# d725-pwm-dco.net
KiCad netlist of a schematic drawn in EAGLE
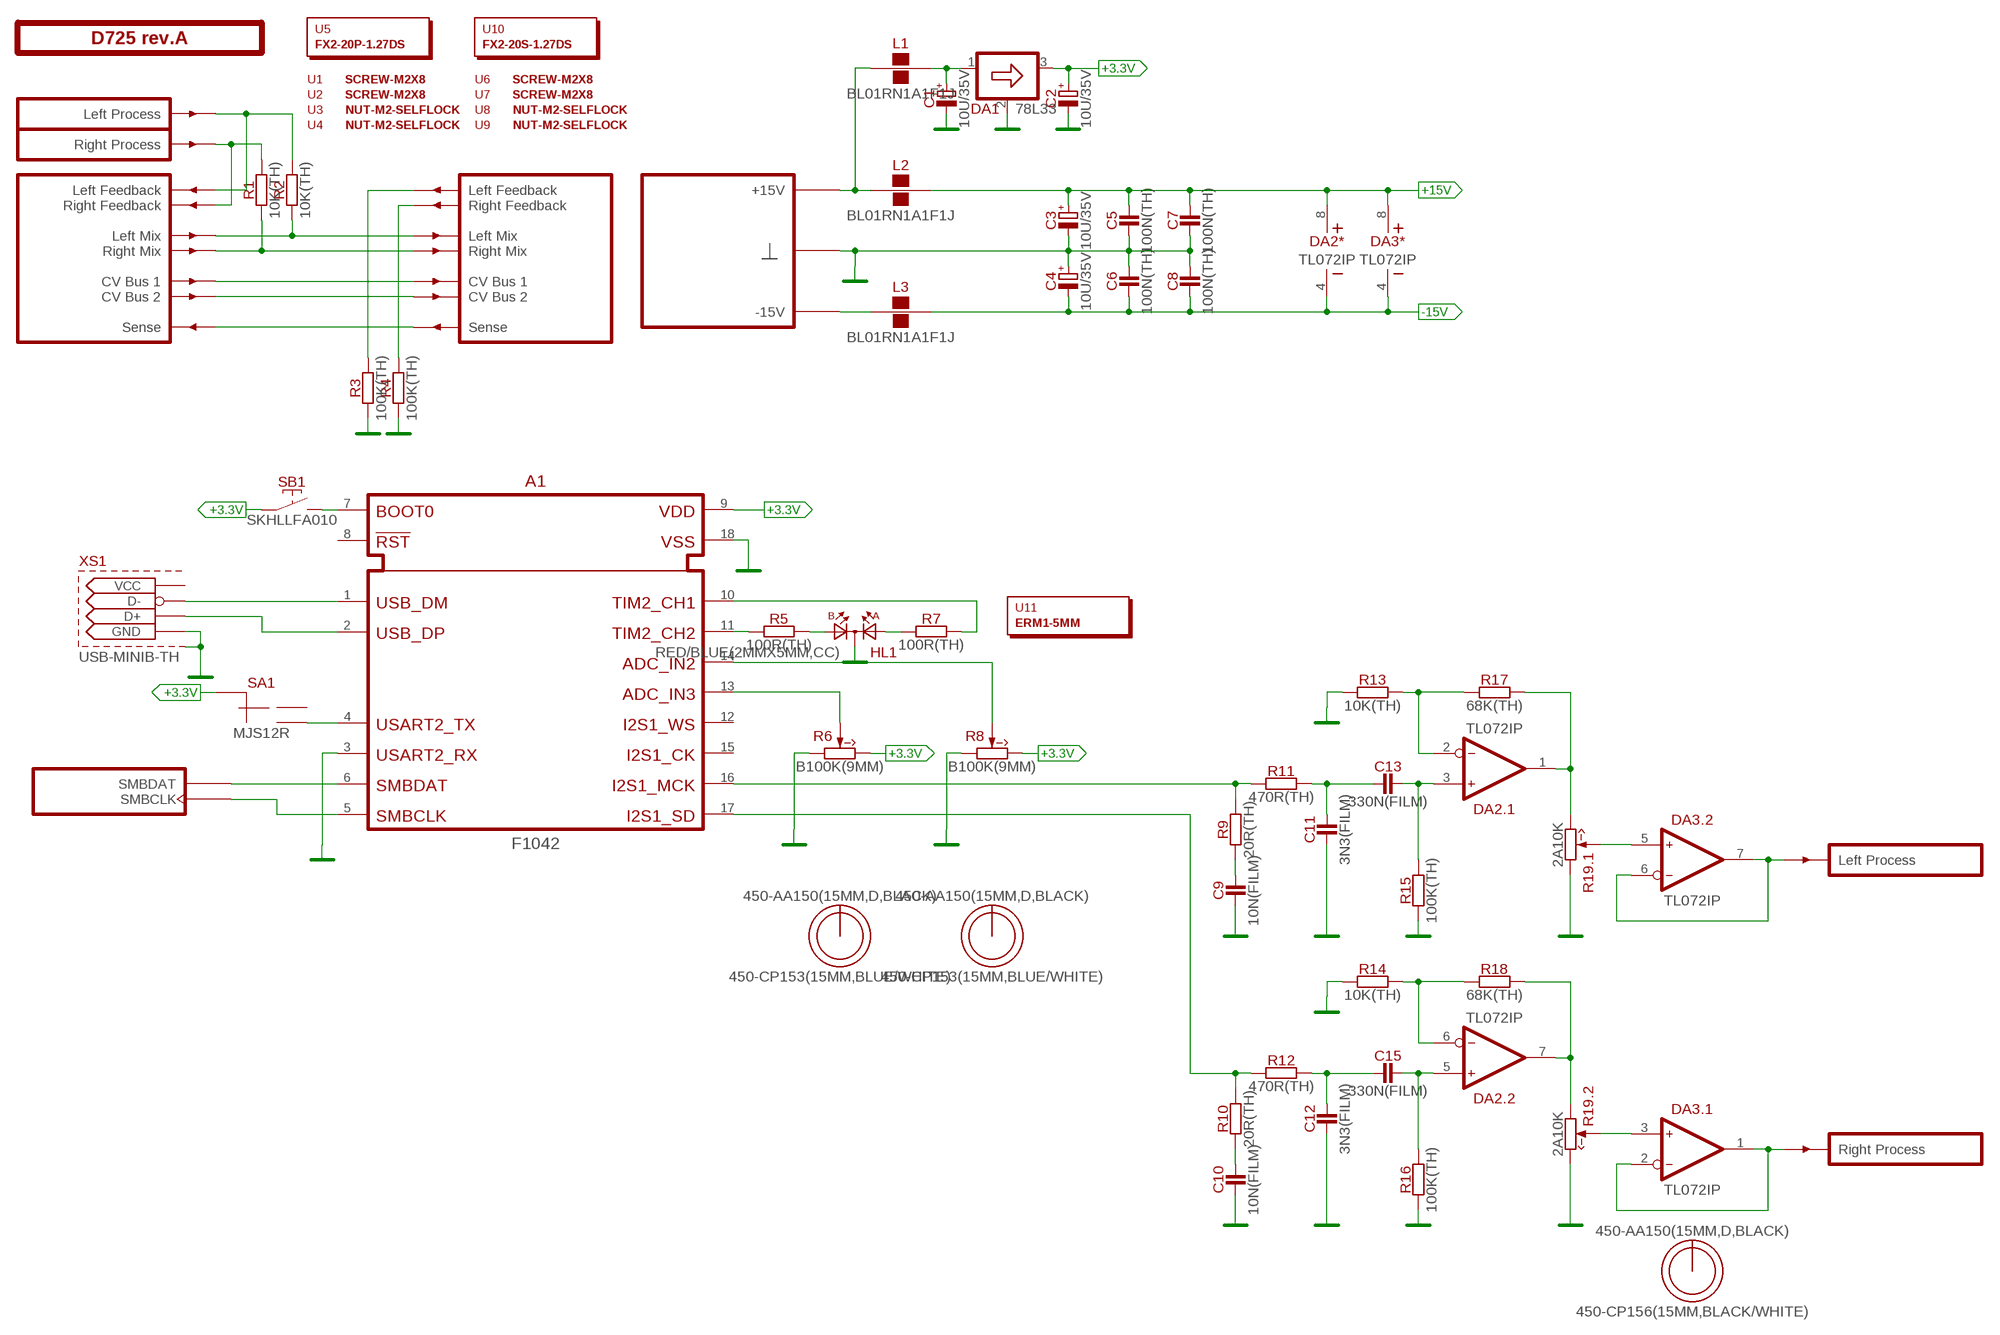
[diagram p0: schematic, sheet 1]

(export (version "E")
  (design (tool "Eeschema 10.0.6"))
  (components
    (comp (ref "A1")
      (value "F1042")
      (footprint "eagle-import:F-DIP18")
      (libsource (lib "eagle-import") (part "F1042"))
    )
    (comp (ref "C1")
      (value "10U/35V")
      (footprint "eagle-import:E2-5")
      (libsource (lib "eagle-import") (part "?10U/35V"))
    )
    (comp (ref "C2")
      (value "10U/35V")
      (footprint "eagle-import:E2-5")
      (libsource (lib "eagle-import") (part "?10U/35V"))
    )
    (comp (ref "C3")
      (value "10U/35V")
      (footprint "eagle-import:E2-5")
      (libsource (lib "eagle-import") (part "?10U/35V"))
    )
    (comp (ref "C4")
      (value "10U/35V")
      (footprint "eagle-import:E2-5")
      (libsource (lib "eagle-import") (part "?10U/35V"))
    )
    (comp (ref "C5")
      (value "100N(TH)")
      (footprint "eagle-import:C050-024X044")
      (libsource (lib "eagle-import") (part "?100N(TH)"))
    )
    (comp (ref "C6")
      (value "100N(TH)")
      (footprint "eagle-import:C050-024X044")
      (libsource (lib "eagle-import") (part "?100N(TH)"))
    )
    (comp (ref "C7")
      (value "100N(TH)")
      (footprint "eagle-import:C050-024X044")
      (libsource (lib "eagle-import") (part "?100N(TH)"))
    )
    (comp (ref "C8")
      (value "100N(TH)")
      (footprint "eagle-import:C050-024X044")
      (libsource (lib "eagle-import") (part "?100N(TH)"))
    )
    (comp (ref "C9")
      (value "10N(FILM)")
      (footprint "eagle-import:C050-025X075")
      (libsource (lib "eagle-import") (part "?10N(FILM)"))
    )
    (comp (ref "C10")
      (value "10N(FILM)")
      (footprint "eagle-import:C050-025X075")
      (libsource (lib "eagle-import") (part "?10N(FILM)"))
    )
    (comp (ref "C11")
      (value "3N3(FILM)")
      (footprint "eagle-import:C050-025X075")
      (libsource (lib "eagle-import") (part "?3N3(FILM)"))
    )
    (comp (ref "C12")
      (value "3N3(FILM)")
      (footprint "eagle-import:C050-025X075")
      (libsource (lib "eagle-import") (part "?3N3(FILM)"))
    )
    (comp (ref "C13")
      (value "330N(FILM)")
      (footprint "eagle-import:C050-035X075")
      (libsource (lib "eagle-import") (part "?330N(FILM)"))
    )
    (comp (ref "C15")
      (value "330N(FILM)")
      (footprint "eagle-import:C050-035X075")
      (libsource (lib "eagle-import") (part "?330N(FILM)"))
    )
    (comp (ref "DA1")
      (value "78L33")
      (footprint "eagle-import:TO92")
      (libsource (lib "eagle-import") (part "78L33"))
    )
    (comp (ref "DA2")
      (value "TL072IP")
      (footprint "eagle-import:DIP-8")
      (libsource (lib "eagle-import") (part "TL072IP"))
    )
    (comp (ref "DA3")
      (value "TL072IP")
      (footprint "eagle-import:DIP-8")
      (libsource (lib "eagle-import") (part "TL072IP"))
    )
    (comp (ref "HL1")
      (value "RED/BLUE(2MMX5MM,CC)")
      (footprint "eagle-import:LED2X5-3PIN")
      (libsource (lib "eagle-import") (part "?(2MMX5MM,CC)RED/BLUE"))
    )
    (comp (ref "L1")
      (value "BL01RN1A1F1J")
      (footprint "eagle-import:BL01RN1A")
      (libsource (lib "eagle-import") (part "BL01RN1A?1F1J"))
    )
    (comp (ref "L2")
      (value "BL01RN1A1F1J")
      (footprint "eagle-import:BL01RN1A")
      (libsource (lib "eagle-import") (part "BL01RN1A?1F1J"))
    )
    (comp (ref "L3")
      (value "BL01RN1A1F1J")
      (footprint "eagle-import:BL01RN1A")
      (libsource (lib "eagle-import") (part "BL01RN1A?1F1J"))
    )
    (comp (ref "O1")
      (value "450-AA150(15MM,D,BLACK)")
      (footprint "eagle-import:EMPTY")
      (libsource (lib "eagle-import") (part "450-AA?150(15MM,D,BLACK)"))
    )
    (comp (ref "O2")
      (value "450-CP153(15MM,BLUE/WHITE)")
      (footprint "eagle-import:EMPTY")
      (libsource (lib "eagle-import") (part "450-C?P153(15MM,BLUE/WHITE)"))
    )
    (comp (ref "O3")
      (value "450-AA150(15MM,D,BLACK)")
      (footprint "eagle-import:EMPTY")
      (libsource (lib "eagle-import") (part "450-AA?150(15MM,D,BLACK)"))
    )
    (comp (ref "O4")
      (value "450-CP153(15MM,BLUE/WHITE)")
      (footprint "eagle-import:EMPTY")
      (libsource (lib "eagle-import") (part "450-C?P153(15MM,BLUE/WHITE)"))
    )
    (comp (ref "O5")
      (value "450-AA150(15MM,D,BLACK)")
      (footprint "eagle-import:EMPTY")
      (libsource (lib "eagle-import") (part "450-AA?150(15MM,D,BLACK)"))
    )
    (comp (ref "O6")
      (value "450-CP156(15MM,BLACK/WHITE)")
      (footprint "eagle-import:EMPTY")
      (libsource (lib "eagle-import") (part "450-C?P156(15MM,BLACK/WHITE)"))
    )
    (comp (ref "PCB1")
      (value "D725 rev.A")
      (footprint "eagle-import:ST2-BOARD-50")
      (libsource (lib "eagle-import") (part "ST2-BOARD-?50"))
    )
    (comp (ref "R1")
      (value "10K(TH)")
      (footprint "eagle-import:R-0207_10")
      (libsource (lib "eagle-import") (part "?10K(TH)"))
    )
    (comp (ref "R2")
      (value "10K(TH)")
      (footprint "eagle-import:R-0207_10")
      (libsource (lib "eagle-import") (part "?10K(TH)"))
    )
    (comp (ref "R3")
      (value "100K(TH)")
      (footprint "eagle-import:R-0207_10")
      (libsource (lib "eagle-import") (part "?100K(TH)"))
    )
    (comp (ref "R4")
      (value "100K(TH)")
      (footprint "eagle-import:R-0207_10")
      (libsource (lib "eagle-import") (part "?100K(TH)"))
    )
    (comp (ref "R5")
      (value "100R(TH)")
      (footprint "eagle-import:R-0207_10")
      (libsource (lib "eagle-import") (part "?100R(TH)"))
    )
    (comp (ref "R6")
      (value "B100K(9MM)")
      (footprint "eagle-import:RV09-SINGLE")
      (libsource (lib "eagle-import") (part "?B100K(9MM)"))
    )
    (comp (ref "R7")
      (value "100R(TH)")
      (footprint "eagle-import:R-0207_10")
      (libsource (lib "eagle-import") (part "?100R(TH)"))
    )
    (comp (ref "R8")
      (value "B100K(9MM)")
      (footprint "eagle-import:RV09-SINGLE")
      (libsource (lib "eagle-import") (part "?B100K(9MM)"))
    )
    (comp (ref "R9")
      (value "20R(TH)")
      (footprint "eagle-import:R-0207_10")
      (libsource (lib "eagle-import") (part "?20R(TH)"))
    )
    (comp (ref "R10")
      (value "20R(TH)")
      (footprint "eagle-import:R-0207_10")
      (libsource (lib "eagle-import") (part "?20R(TH)"))
    )
    (comp (ref "R11")
      (value "470R(TH)")
      (footprint "eagle-import:R-0207_10")
      (libsource (lib "eagle-import") (part "?470R(TH)"))
    )
    (comp (ref "R12")
      (value "470R(TH)")
      (footprint "eagle-import:R-0207_10")
      (libsource (lib "eagle-import") (part "?470R(TH)"))
    )
    (comp (ref "R13")
      (value "10K(TH)")
      (footprint "eagle-import:R-0207_10")
      (libsource (lib "eagle-import") (part "?10K(TH)"))
    )
    (comp (ref "R14")
      (value "10K(TH)")
      (footprint "eagle-import:R-0207_10")
      (libsource (lib "eagle-import") (part "?10K(TH)"))
    )
    (comp (ref "R15")
      (value "100K(TH)")
      (footprint "eagle-import:R-0207_10")
      (libsource (lib "eagle-import") (part "?100K(TH)"))
    )
    (comp (ref "R16")
      (value "100K(TH)")
      (footprint "eagle-import:R-0207_10")
      (libsource (lib "eagle-import") (part "?100K(TH)"))
    )
    (comp (ref "R17")
      (value "68K(TH)")
      (footprint "eagle-import:R-0207_10")
      (libsource (lib "eagle-import") (part "?68K(TH)"))
    )
    (comp (ref "R18")
      (value "68K(TH)")
      (footprint "eagle-import:R-0207_10")
      (libsource (lib "eagle-import") (part "?68K(TH)"))
    )
    (comp (ref "R19")
      (value "2A10K")
      (footprint "eagle-import:RV11-DUAL")
      (libsource (lib "eagle-import") (part "2?A10K"))
    )
    (comp (ref "SA1")
      (value "MJS12R")
      (footprint "eagle-import:APEM-MJS12R")
      (libsource (lib "eagle-import") (part "MJS12R"))
    )
    (comp (ref "SB1")
      (value "SKHLLFA010")
      (footprint "eagle-import:SKHLLFA010")
      (libsource (lib "eagle-import") (part "SKHLLFA010"))
    )
    (comp (ref "U1")
      (value "SCREW-M2X8")
      (footprint "eagle-import:EMPTY")
      (libsource (lib "eagle-import") (part "?SCREW-M2X8"))
    )
    (comp (ref "U2")
      (value "SCREW-M2X8")
      (footprint "eagle-import:EMPTY")
      (libsource (lib "eagle-import") (part "?SCREW-M2X8"))
    )
    (comp (ref "U3")
      (value "NUT-M2-SELFLOCK")
      (footprint "eagle-import:EMPTY")
      (libsource (lib "eagle-import") (part "?NUT-M2-SELFLOCK"))
    )
    (comp (ref "U4")
      (value "NUT-M2-SELFLOCK")
      (footprint "eagle-import:EMPTY")
      (libsource (lib "eagle-import") (part "?NUT-M2-SELFLOCK"))
    )
    (comp (ref "U5")
      (value "FX2-20P-1.27DS")
      (footprint "eagle-import:EMPTY")
      (libsource (lib "eagle-import") (part "?FX2-20P-1.27DS"))
    )
    (comp (ref "U6")
      (value "SCREW-M2X8")
      (footprint "eagle-import:EMPTY")
      (libsource (lib "eagle-import") (part "?SCREW-M2X8"))
    )
    (comp (ref "U7")
      (value "SCREW-M2X8")
      (footprint "eagle-import:EMPTY")
      (libsource (lib "eagle-import") (part "?SCREW-M2X8"))
    )
    (comp (ref "U8")
      (value "NUT-M2-SELFLOCK")
      (footprint "eagle-import:EMPTY")
      (libsource (lib "eagle-import") (part "?NUT-M2-SELFLOCK"))
    )
    (comp (ref "U9")
      (value "NUT-M2-SELFLOCK")
      (footprint "eagle-import:EMPTY")
      (libsource (lib "eagle-import") (part "?NUT-M2-SELFLOCK"))
    )
    (comp (ref "U10")
      (value "FX2-20S-1.27DS")
      (footprint "eagle-import:EMPTY")
      (libsource (lib "eagle-import") (part "?FX2-20S-1.27DS"))
    )
    (comp (ref "U11")
      (value "ERM1-5MM")
      (footprint "eagle-import:EMPTY")
      (libsource (lib "eagle-import") (part "?ERM1-5MM"))
    )
    (comp (ref "XS1")
      (value "USB-MINIB-TH")
      (footprint "eagle-import:USB-MB-H")
      (libsource (lib "eagle-import") (part "USB-MINIB-TH"))
    )
  )
  (nets
    (net (code "1") (name "+3.3V") (class "Default")
      (node (ref "A1") (pin "9") (pinfunction "VDD_9") (pintype "input"))
      (node (ref "C2") (pin "+") (pinfunction "+_+") (pintype "passive"))
      (node (ref "DA1") (pin "3") (pinfunction "OUT_3") (pintype "power_in"))
      (node (ref "R6") (pin "3") (pinfunction "CW_3") (pintype "passive"))
      (node (ref "R8") (pin "3") (pinfunction "CW_3") (pintype "passive"))
      (node (ref "SA1") (pin "C") (pinfunction "CM_C") (pintype "passive"))
      (node (ref "SB1") (pin "1") (pinfunction "1_1") (pintype "passive"))
    )
    (net (code "2") (name "+15V") (class "Default")
      (node (ref "C3") (pin "+") (pinfunction "+_+") (pintype "passive"))
      (node (ref "C5") (pin "2") (pinfunction "2_2") (pintype "passive"))
      (node (ref "C7") (pin "2") (pinfunction "2_2") (pintype "passive"))
      (node (ref "DA2") (pin "8") (pinfunction "V+_8") (pintype "power_in"))
      (node (ref "DA3") (pin "8") (pinfunction "V+_8") (pintype "power_in"))
      (node (ref "L2") (pin "2") (pinfunction "2_2") (pintype "passive"))
    )
    (net (code "3") (name "-15V") (class "Default")
      (node (ref "C4") (pin "-") (pinfunction "-_-") (pintype "passive"))
      (node (ref "C6") (pin "1") (pinfunction "1_1") (pintype "passive"))
      (node (ref "C8") (pin "1") (pinfunction "1_1") (pintype "passive"))
      (node (ref "DA2") (pin "4") (pinfunction "V-_4") (pintype "power_in"))
      (node (ref "DA3") (pin "4") (pinfunction "V-_4") (pintype "power_in"))
      (node (ref "L3") (pin "2") (pinfunction "2_2") (pintype "passive"))
    )
    (net (code "4") (name "GND") (class "Default")
      (node (ref "A1") (pin "18") (pinfunction "VSS_18") (pintype "input"))
      (node (ref "A1") (pin "3") (pinfunction "USART2_RX_3") (pintype "input"))
      (node (ref "C1") (pin "-") (pinfunction "-_-") (pintype "passive"))
      (node (ref "C10") (pin "1") (pinfunction "1_1") (pintype "passive"))
      (node (ref "C11") (pin "1") (pinfunction "1_1") (pintype "passive"))
      (node (ref "C12") (pin "1") (pinfunction "1_1") (pintype "passive"))
      (node (ref "C2") (pin "-") (pinfunction "-_-") (pintype "passive"))
      (node (ref "C3") (pin "-") (pinfunction "-_-") (pintype "passive"))
      (node (ref "C4") (pin "+") (pinfunction "+_+") (pintype "passive"))
      (node (ref "C5") (pin "1") (pinfunction "1_1") (pintype "passive"))
      (node (ref "C6") (pin "2") (pinfunction "2_2") (pintype "passive"))
      (node (ref "C7") (pin "1") (pinfunction "1_1") (pintype "passive"))
      (node (ref "C8") (pin "2") (pinfunction "2_2") (pintype "passive"))
      (node (ref "C9") (pin "1") (pinfunction "1_1") (pintype "passive"))
      (node (ref "DA1") (pin "2") (pinfunction "GND_2") (pintype "power_in"))
      (node (ref "HL1") (pin "K") (pinfunction "K_K") (pintype "passive"))
      (node (ref "PCB1") (pin "B4") (pinfunction "GND_B4") (pintype "bidirectional"))
      (node (ref "PCB1") (pin "B4'") (pinfunction "GND_B4'") (pintype "bidirectional"))
      (node (ref "PCB1") (pin "B5") (pinfunction "GND_B5") (pintype "bidirectional"))
      (node (ref "PCB1") (pin "B5'") (pinfunction "GND_B5'") (pintype "bidirectional"))
      (node (ref "PCB1") (pin "B6") (pinfunction "GND_B6") (pintype "bidirectional"))
      (node (ref "PCB1") (pin "B6'") (pinfunction "GND_B6'") (pintype "bidirectional"))
      (node (ref "PCB1") (pin "B7") (pinfunction "GND_B7") (pintype "bidirectional"))
      (node (ref "PCB1") (pin "B7'") (pinfunction "GND_B7'") (pintype "bidirectional"))
      (node (ref "PCB1") (pin "B8") (pinfunction "GND_B8") (pintype "bidirectional"))
      (node (ref "PCB1") (pin "B8'") (pinfunction "GND_B8'") (pintype "bidirectional"))
      (node (ref "R13") (pin "1") (pinfunction "1_1") (pintype "passive"))
      (node (ref "R14") (pin "1") (pinfunction "1_1") (pintype "passive"))
      (node (ref "R15") (pin "1") (pinfunction "1_1") (pintype "passive"))
      (node (ref "R16") (pin "1") (pinfunction "1_1") (pintype "passive"))
      (node (ref "R19") (pin "1") (pinfunction "CCW_1") (pintype "passive"))
      (node (ref "R19") (pin "3'") (pinfunction "CW_3'") (pintype "passive"))
      (node (ref "R3") (pin "1") (pinfunction "1_1") (pintype "passive"))
      (node (ref "R4") (pin "1") (pinfunction "1_1") (pintype "passive"))
      (node (ref "R6") (pin "1") (pinfunction "CCW_1") (pintype "passive"))
      (node (ref "R8") (pin "1") (pinfunction "CCW_1") (pintype "passive"))
      (node (ref "XS1") (pin "GND") (pinfunction "GND_GND") (pintype "passive"))
      (node (ref "XS1") (pin "P$1") (pinfunction "S1_P$1") (pintype "passive"))
      (node (ref "XS1") (pin "P$2") (pinfunction "S1_P$2") (pintype "passive"))
      (node (ref "XS1") (pin "P$6") (pinfunction "S1_P$6") (pintype "passive"))
      (node (ref "XS1") (pin "P$7") (pinfunction "S1_P$7") (pintype "passive"))
    )
    (net (code "5") (name "Net-(A1-ADC_IN2)") (class "Default")
      (node (ref "A1") (pin "14") (pinfunction "ADC_IN2_14") (pintype "input"))
      (node (ref "R8") (pin "2") (pinfunction "W_2") (pintype "passive"))
    )
    (net (code "6") (name "Net-(A1-ADC_IN3)") (class "Default")
      (node (ref "A1") (pin "13") (pinfunction "ADC_IN3_13") (pintype "input"))
      (node (ref "R6") (pin "2") (pinfunction "W_2") (pintype "passive"))
    )
    (net (code "7") (name "Net-(A1-BOOT0)") (class "Default")
      (node (ref "A1") (pin "7") (pinfunction "BOOT0_7") (pintype "input"))
      (node (ref "SB1") (pin "2") (pinfunction "2_2") (pintype "passive"))
    )
    (net (code "8") (name "Net-(A1-I2S1_MCK)") (class "Default")
      (node (ref "A1") (pin "16") (pinfunction "I2S1_MCK_16") (pintype "input"))
      (node (ref "R11") (pin "1") (pinfunction "1_1") (pintype "passive"))
      (node (ref "R9") (pin "2") (pinfunction "2_2") (pintype "passive"))
    )
    (net (code "9") (name "Net-(A1-I2S1_SD)") (class "Default")
      (node (ref "A1") (pin "17") (pinfunction "I2S1_SD_17") (pintype "input"))
      (node (ref "R10") (pin "2") (pinfunction "2_2") (pintype "passive"))
      (node (ref "R12") (pin "1") (pinfunction "1_1") (pintype "passive"))
    )
    (net (code "10") (name "Net-(A1-SBMDAT)") (class "Default")
      (node (ref "A1") (pin "6") (pinfunction "SBMDAT_6") (pintype "input"))
      (node (ref "PCB1") (pin "ASMBDAT") (pinfunction "SMBDAT_ASMBDAT") (pintype "bidirectional"))
      (node (ref "PCB1") (pin "ASMBDAT'") (pinfunction "SMBDAT_ASMBDAT'") (pintype "bidirectional"))
    )
    (net (code "11") (name "Net-(A1-SMBCLK)") (class "Default")
      (node (ref "A1") (pin "5") (pinfunction "SMBCLK_5") (pintype "input"))
      (node (ref "PCB1") (pin "ASMBCLK") (pinfunction "SMBCLK_ASMBCLK") (pintype "bidirectional"))
      (node (ref "PCB1") (pin "ASMBCLK'") (pinfunction "SMBCLK_ASMBCLK'") (pintype "bidirectional"))
    )
    (net (code "12") (name "Net-(A1-TIM2_CH1)") (class "Default")
      (node (ref "A1") (pin "10") (pinfunction "TIM2_CH1_10") (pintype "input"))
      (node (ref "R7") (pin "2") (pinfunction "2_2") (pintype "passive"))
    )
    (net (code "13") (name "Net-(A1-TIM2_CH2)") (class "Default")
      (node (ref "A1") (pin "11") (pinfunction "TIM2_CH2_11") (pintype "input"))
      (node (ref "R5") (pin "1") (pinfunction "1_1") (pintype "passive"))
    )
    (net (code "14") (name "Net-(A1-USART2_TX)") (class "Default")
      (node (ref "A1") (pin "4") (pinfunction "USART2_TX_4") (pintype "input"))
      (node (ref "SA1") (pin "NO") (pinfunction "2_NO") (pintype "passive"))
    )
    (net (code "15") (name "Net-(A1-USB_DM)") (class "Default")
      (node (ref "A1") (pin "1") (pinfunction "USB_DM_1") (pintype "input"))
      (node (ref "XS1") (pin "D-") (pinfunction "D-_D-") (pintype "bidirectional"))
    )
    (net (code "16") (name "Net-(A1-USB_DP)") (class "Default")
      (node (ref "A1") (pin "2") (pinfunction "USB_DP_2") (pintype "input"))
      (node (ref "XS1") (pin "D+") (pinfunction "D+_D+") (pintype "bidirectional"))
    )
    (net (code "17") (name "Net-(C9-Pad2)") (class "Default")
      (node (ref "C9") (pin "2") (pinfunction "2_2") (pintype "passive"))
      (node (ref "R9") (pin "1") (pinfunction "1_1") (pintype "passive"))
    )
    (net (code "18") (name "Net-(C10-Pad2)") (class "Default")
      (node (ref "C10") (pin "2") (pinfunction "2_2") (pintype "passive"))
      (node (ref "R10") (pin "1") (pinfunction "1_1") (pintype "passive"))
    )
    (net (code "19") (name "Net-(C11-Pad2)") (class "Default")
      (node (ref "C11") (pin "2") (pinfunction "2_2") (pintype "passive"))
      (node (ref "C13") (pin "1") (pinfunction "1_1") (pintype "passive"))
      (node (ref "R11") (pin "2") (pinfunction "2_2") (pintype "passive"))
    )
    (net (code "20") (name "Net-(C12-Pad2)") (class "Default")
      (node (ref "C12") (pin "2") (pinfunction "2_2") (pintype "passive"))
      (node (ref "C15") (pin "1") (pinfunction "1_1") (pintype "passive"))
      (node (ref "R12") (pin "2") (pinfunction "2_2") (pintype "passive"))
    )
    (net (code "21") (name "Net-(DA1-IN)") (class "Default")
      (node (ref "C1") (pin "+") (pinfunction "+_+") (pintype "passive"))
      (node (ref "DA1") (pin "1") (pinfunction "IN_1") (pintype "power_in"))
      (node (ref "L1") (pin "2") (pinfunction "2_2") (pintype "passive"))
    )
    (net (code "22") (name "Net-(DA2B-IN+)") (class "Default")
      (node (ref "C13") (pin "2") (pinfunction "2_2") (pintype "passive"))
      (node (ref "DA2") (pin "3") (pinfunction "IN+_3") (pintype "input"))
      (node (ref "R15") (pin "2") (pinfunction "2_2") (pintype "passive"))
    )
    (net (code "23") (name "Net-(DA2B-IN-)") (class "Default")
      (node (ref "DA2") (pin "2") (pinfunction "IN-_2") (pintype "input"))
      (node (ref "R13") (pin "2") (pinfunction "2_2") (pintype "passive"))
      (node (ref "R17") (pin "1") (pinfunction "1_1") (pintype "passive"))
    )
    (net (code "24") (name "Net-(DA2B-OUT)") (class "Default")
      (node (ref "DA2") (pin "1") (pinfunction "OUT_1") (pintype "output"))
      (node (ref "R17") (pin "2") (pinfunction "2_2") (pintype "passive"))
      (node (ref "R19") (pin "3") (pinfunction "CW_3") (pintype "passive"))
    )
    (net (code "25") (name "Net-(DA2C-IN+)") (class "Default")
      (node (ref "C15") (pin "2") (pinfunction "2_2") (pintype "passive"))
      (node (ref "DA2") (pin "5") (pinfunction "IN+_5") (pintype "input"))
      (node (ref "R16") (pin "2") (pinfunction "2_2") (pintype "passive"))
    )
    (net (code "26") (name "Net-(DA2C-IN-)") (class "Default")
      (node (ref "DA2") (pin "6") (pinfunction "IN-_6") (pintype "input"))
      (node (ref "R14") (pin "2") (pinfunction "2_2") (pintype "passive"))
      (node (ref "R18") (pin "1") (pinfunction "1_1") (pintype "passive"))
    )
    (net (code "27") (name "Net-(DA2C-OUT)") (class "Default")
      (node (ref "DA2") (pin "7") (pinfunction "OUT_7") (pintype "output"))
      (node (ref "R18") (pin "2") (pinfunction "2_2") (pintype "passive"))
      (node (ref "R19") (pin "1'") (pinfunction "CCW_1'") (pintype "passive"))
    )
    (net (code "28") (name "Net-(DA3B-IN+)") (class "Default")
      (node (ref "DA3") (pin "3") (pinfunction "IN+_3") (pintype "input"))
      (node (ref "R19") (pin "2'") (pinfunction "W_2'") (pintype "passive"))
    )
    (net (code "29") (name "Net-(DA3B-IN-)") (class "Default")
      (node (ref "DA3") (pin "1") (pinfunction "OUT_1") (pintype "output"))
      (node (ref "DA3") (pin "2") (pinfunction "IN-_2") (pintype "input"))
      (node (ref "PCB1") (pin "BOUTR'") (pinfunction "OUTR_BOUTR'") (pintype "bidirectional"))
    )
    (net (code "30") (name "Net-(DA3C-IN+)") (class "Default")
      (node (ref "DA3") (pin "5") (pinfunction "IN+_5") (pintype "input"))
      (node (ref "R19") (pin "2") (pinfunction "W_2") (pintype "passive"))
    )
    (net (code "31") (name "Net-(DA3C-IN-)") (class "Default")
      (node (ref "DA3") (pin "6") (pinfunction "IN-_6") (pintype "input"))
      (node (ref "DA3") (pin "7") (pinfunction "OUT_7") (pintype "output"))
      (node (ref "PCB1") (pin "BOUTL'") (pinfunction "OUTL_BOUTL'") (pintype "bidirectional"))
    )
    (net (code "32") (name "Net-(HL1-PadA1)") (class "Default")
      (node (ref "HL1") (pin "A1") (pinfunction "A1_A1") (pintype "passive"))
      (node (ref "R7") (pin "1") (pinfunction "1_1") (pintype "passive"))
    )
    (net (code "33") (name "Net-(HL1-PadA2)") (class "Default")
      (node (ref "HL1") (pin "A2") (pinfunction "A2_A2") (pintype "passive"))
      (node (ref "R5") (pin "2") (pinfunction "2_2") (pintype "passive"))
    )
    (net (code "34") (name "Net-(L1-Pad1)") (class "Default")
      (node (ref "L1") (pin "1") (pinfunction "1_1") (pintype "passive"))
      (node (ref "L2") (pin "1") (pinfunction "1_1") (pintype "passive"))
      (node (ref "PCB1") (pin "A+15") (pinfunction "P+15V_A+15") (pintype "bidirectional"))
      (node (ref "PCB1") (pin "A+15'") (pinfunction "P+15V_A+15'") (pintype "bidirectional"))
      (node (ref "PCB1") (pin "B+15") (pinfunction "P+15V_B+15") (pintype "bidirectional"))
      (node (ref "PCB1") (pin "B+15'") (pinfunction "P+15V_B+15'") (pintype "bidirectional"))
    )
    (net (code "35") (name "Net-(L3-Pad1)") (class "Default")
      (node (ref "L3") (pin "1") (pinfunction "1_1") (pintype "passive"))
      (node (ref "PCB1") (pin "A-15") (pinfunction "P-15V_A-15") (pintype "bidirectional"))
      (node (ref "PCB1") (pin "A-15'") (pinfunction "P-15V_A-15'") (pintype "bidirectional"))
      (node (ref "PCB1") (pin "B-15") (pinfunction "P-15V_B-15") (pintype "bidirectional"))
      (node (ref "PCB1") (pin "B-15'") (pinfunction "P-15V_B-15'") (pintype "bidirectional"))
    )
    (net (code "36") (name "Net-(PCB1B-INL)") (class "Default")
      (node (ref "PCB1") (pin "ALFBK") (pinfunction "LFBK_ALFBK") (pintype "bidirectional"))
      (node (ref "PCB1") (pin "BINL") (pinfunction "INL_BINL") (pintype "bidirectional"))
      (node (ref "R2") (pin "2") (pinfunction "2_2") (pintype "passive"))
    )
    (net (code "37") (name "Net-(PCB1C-INR)") (class "Default")
      (node (ref "PCB1") (pin "ARFBK") (pinfunction "RFBK_ARFBK") (pintype "bidirectional"))
      (node (ref "PCB1") (pin "BINR") (pinfunction "INR_BINR") (pintype "bidirectional"))
      (node (ref "R1") (pin "2") (pinfunction "2_2") (pintype "passive"))
    )
    (net (code "38") (name "Net-(PCB1F-CV1)") (class "Default")
      (node (ref "PCB1") (pin "ACV1") (pinfunction "CV1_ACV1") (pintype "bidirectional"))
      (node (ref "PCB1") (pin "ACV1'") (pinfunction "CV1'_ACV1'") (pintype "bidirectional"))
    )
    (net (code "39") (name "Net-(PCB1F-CV2)") (class "Default")
      (node (ref "PCB1") (pin "ACV2") (pinfunction "CV2_ACV2") (pintype "bidirectional"))
      (node (ref "PCB1") (pin "ACV2'") (pinfunction "CV2'_ACV2'") (pintype "bidirectional"))
    )
    (net (code "40") (name "Net-(PCB1F-LMIX)") (class "Default")
      (node (ref "PCB1") (pin "ALMIX") (pinfunction "LMIX_ALMIX") (pintype "bidirectional"))
      (node (ref "PCB1") (pin "ALMIX'") (pinfunction "LMIX'_ALMIX'") (pintype "bidirectional"))
      (node (ref "R2") (pin "1") (pinfunction "1_1") (pintype "passive"))
    )
    (net (code "41") (name "Net-(PCB1F-RMIX)") (class "Default")
      (node (ref "PCB1") (pin "ARMIX") (pinfunction "RMIX_ARMIX") (pintype "bidirectional"))
      (node (ref "PCB1") (pin "ARMIX'") (pinfunction "RMIX'_ARMIX'") (pintype "bidirectional"))
      (node (ref "R1") (pin "1") (pinfunction "1_1") (pintype "passive"))
    )
    (net (code "42") (name "Net-(PCB1F-SENSE)") (class "Default")
      (node (ref "PCB1") (pin "BSENSE") (pinfunction "SENSE_BSENSE") (pintype "bidirectional"))
      (node (ref "PCB1") (pin "BSENSE'") (pinfunction "SENSE'_BSENSE'") (pintype "bidirectional"))
    )
    (net (code "43") (name "Net-(PCB1G-LFBK')") (class "Default")
      (node (ref "PCB1") (pin "ALFBK'") (pinfunction "LFBK'_ALFBK'") (pintype "bidirectional"))
      (node (ref "R3") (pin "2") (pinfunction "2_2") (pintype "passive"))
    )
    (net (code "44") (name "Net-(PCB1G-RFBK')") (class "Default")
      (node (ref "PCB1") (pin "ARFBK'") (pinfunction "RFBK'_ARFBK'") (pintype "bidirectional"))
      (node (ref "R4") (pin "2") (pinfunction "2_2") (pintype "passive"))
    )
    (net (code "45") (name "unconnected-(A1-I2S1_CK-Pad15)") (class "Default")
      (node (ref "A1") (pin "15") (pinfunction "I2S1_CK_15") (pintype "input"))
    )
    (net (code "46") (name "unconnected-(A1-I2S1_WS-Pad12)") (class "Default")
      (node (ref "A1") (pin "12") (pinfunction "I2S1_WS_12") (pintype "input"))
    )
    (net (code "47") (name "unconnected-(A1-~{RST}-Pad8)") (class "Default")
      (node (ref "A1") (pin "8") (pinfunction "~{RST}_8") (pintype "input"))
    )
    (net (code "48") (name "unconnected-(SA1-1-PadNC)") (class "Default")
      (node (ref "SA1") (pin "NC") (pinfunction "1_NC") (pintype "passive"))
    )
    (net (code "49") (name "unconnected-(XS1-VCC-PadVBUS)") (class "Default")
      (node (ref "XS1") (pin "VBUS") (pinfunction "VCC_VBUS") (pintype "passive"))
    )
  )
)
